# 1-Schematic_EMWAVER_ONE.net
KiCad netlist of a schematic drawn in EasyEDA
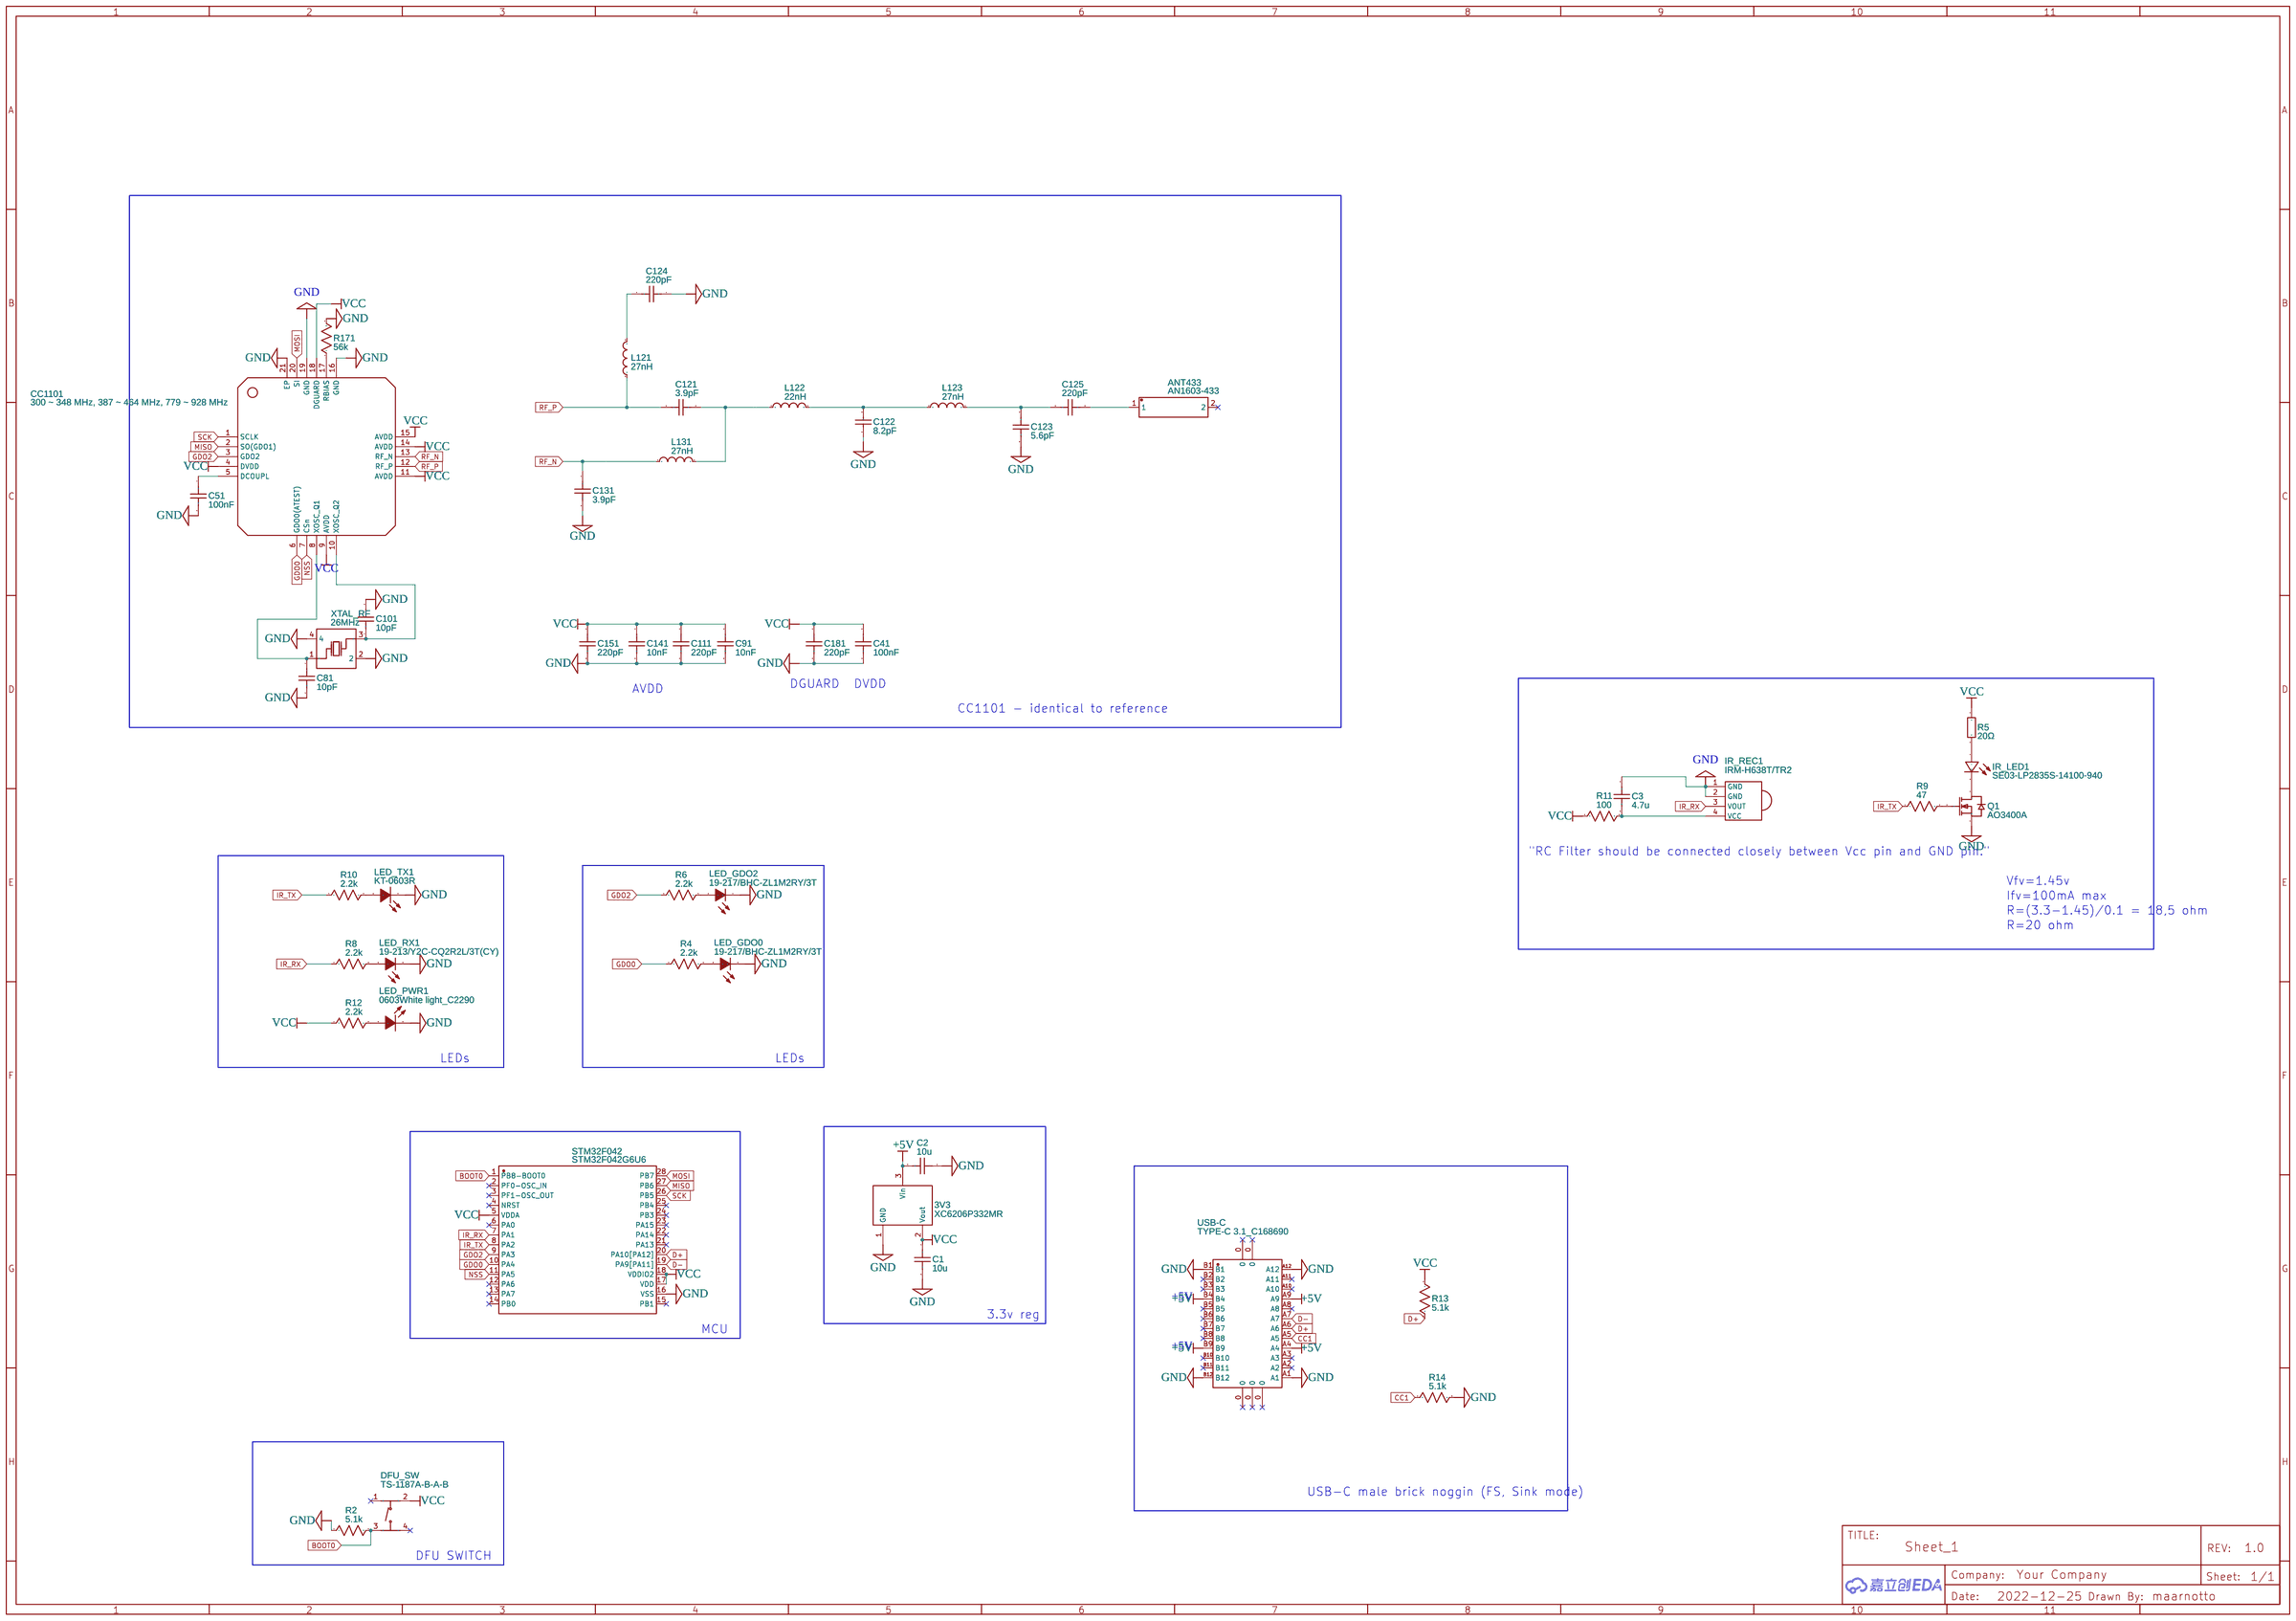
[diagram p0: schematic sheet]

(export (version "E")
  (design (tool "Eeschema 10.0.6"))
  (components
    (comp (ref "3V3")
      (value "XC6206P332MR")
      (fields (field (name "Manufacturer") "TOREX(特瑞仕)"))
      (libsource (lib "") (part "XC6206P332MR"))
    )
    (comp (ref "ANT433")
      (value "AN1603-433")
      (fields (field (name "Manufacturer") "rainsun(霖昱微)"))
      (libsource (lib "") (part "AN1603-433"))
    )
    (comp (ref "C1") (value "10u") (libsource (lib "") (part "C_0603_US")))
    (comp (ref "C2") (value "10u") (libsource (lib "") (part "C_0603_US_1")))
    (comp (ref "C3") (value "4.7u") (libsource (lib "") (part "C_0603_US")))
    (comp (ref "C41") (value "100nF") (libsource (lib "") (part "C_0402_US")))
    (comp (ref "C51") (value "100nF") (libsource (lib "") (part "C_0402_US")))
    (comp (ref "C81") (value "10pF") (libsource (lib "") (part "C_0402_US")))
    (comp (ref "C91") (value "10nF") (libsource (lib "") (part "C_0402_US")))
    (comp (ref "C101") (value "10pF") (libsource (lib "") (part "C_0402_US_2")))
    (comp (ref "C111") (value "220pF") (libsource (lib "") (part "C_0402_US")))
    (comp (ref "C121") (value "3.9pF") (libsource (lib "") (part "C_0402_US_1")))
    (comp (ref "C122")
      (value "8.2pF")
      (fields (field (name "Manufacturer Part") "0402CG8R2C500NT") (field (name "Manufacturer") "FH(风华)"))
      (libsource (lib "") (part "0402CG8R2C500NT"))
    )
    (comp (ref "C123") (value "5.6pF") (libsource (lib "") (part "C_0402_US")))
    (comp (ref "C124") (value "220pF") (libsource (lib "") (part "C_0402_US_1")))
    (comp (ref "C125") (value "220pF") (libsource (lib "") (part "C_0402_US_1")))
    (comp (ref "C131") (value "3.9pF") (libsource (lib "") (part "C_0402_US")))
    (comp (ref "C141") (value "10nF") (libsource (lib "") (part "C_0402_US")))
    (comp (ref "C151") (value "220pF") (libsource (lib "") (part "C_0402_US")))
    (comp (ref "C181") (value "220pF") (libsource (lib "") (part "C_0402_US")))
    (comp (ref "CC1101")
      (value "300 ~ 348 MHz, 387 ~ 464 MHz, 779 ~ 928 MHz")
      (fields (field (name "Manufacturer Part") "CC1101RGPR") (field (name "Manufacturer") "TI(德州仪器)"))
      (libsource (lib "") (part "CC1101RGPR"))
    )
    (comp (ref "DFU_SW")
      (value "TS-1187A-B-A-B")
      (fields (field (name "Manufacturer") "XKB Connectivity(中国星坤)"))
      (libsource (lib "") (part "TS-1187A-B-A-B"))
    )
    (comp (ref "IR_LED1")
      (value "SE03-LP2835S-14100-940")
      (fields (field (name "Manufacturer") "XSSY(旭晟)"))
      (libsource (lib "") (part "SE03-LP2835S-14100-940"))
    )
    (comp (ref "IR_REC1")
      (value "IRM-H638T/TR2")
      (fields (field (name "Manufacturer") "EVERLIGHT(亿光)"))
      (libsource (lib "") (part "IRM-H638T/TR2"))
    )
    (comp (ref "L121") (value "27nH") (libsource (lib "") (part "L0402_US_1")))
    (comp (ref "L122") (value "22nH") (libsource (lib "") (part "L0402_US")))
    (comp (ref "L123") (value "27nH") (libsource (lib "") (part "L0402_US")))
    (comp (ref "L131") (value "27nH") (libsource (lib "") (part "L0402_US")))
    (comp (ref "LED_GDO0")
      (value "19-217/BHC-ZL1M2RY/3T")
      (fields (field (name "Manufacturer") "EVERLIGHT(亿光)"))
      (libsource (lib "") (part "19-217/BHC-ZL1M2RY/3T"))
    )
    (comp (ref "LED_GDO2")
      (value "19-217/BHC-ZL1M2RY/3T")
      (fields (field (name "Manufacturer") "EVERLIGHT(亿光)"))
      (libsource (lib "") (part "19-217/BHC-ZL1M2RY/3T"))
    )
    (comp (ref "LED_PWR1")
      (value "0603White light_C2290")
      (fields (field (name "Manufacturer Part") "KT-0603白灯"))
      (libsource (lib "") (part "0603White light_C2290"))
    )
    (comp (ref "LED_RX1")
      (value "19-213/Y2C-CQ2R2L/3T(CY)")
      (fields (field (name "Manufacturer") "EVERLIGHT(亿光)"))
      (libsource (lib "") (part "19-213/Y2C-CQ2R2L/3T(CY)"))
    )
    (comp (ref "LED_TX1")
      (value "KT-0603R")
      (fields (field (name "Manufacturer") "KENTO"))
      (libsource (lib "") (part "KT-0603R"))
    )
    (comp (ref "Q1")
      (value "AO3400A")
      (fields (field (name "Manufacturer") "AOS"))
      (libsource (lib "") (part "AO3400A"))
    )
    (comp (ref "R2") (value "5.1k") (libsource (lib "") (part "R_0603_US")))
    (comp (ref "R4") (value "2.2k") (libsource (lib "") (part "R_0603_US")))
    (comp (ref "R5")
      (value "20Ω")
      (fields
        (field (name "Manufacturer Part") "1206W4F200JT5E")
        (field (name "Manufacturer") "UNI-ROYAL(厚声)")
      )
      (libsource (lib "") (part "1206W4F200JT5E"))
    )
    (comp (ref "R6") (value "2.2k") (libsource (lib "") (part "R_0603_US")))
    (comp (ref "R8") (value "2.2k") (libsource (lib "") (part "R_0603_US")))
    (comp (ref "R9") (value "47") (libsource (lib "") (part "R_0603_US")))
    (comp (ref "R10") (value "2.2k") (libsource (lib "") (part "R_0603_US")))
    (comp (ref "R11") (value "100") (libsource (lib "") (part "R_0603_US")))
    (comp (ref "R12") (value "2.2k") (libsource (lib "") (part "R_0603_US")))
    (comp (ref "R13") (value "5.1k") (libsource (lib "") (part "R_0603_US_1")))
    (comp (ref "R14") (value "5.1k") (libsource (lib "") (part "R_0603_US")))
    (comp (ref "R171") (value "56k") (libsource (lib "") (part "R_0402_US")))
    (comp (ref "STM32F042")
      (value "STM32F042G6U6")
      (fields (field (name "Manufacturer") "ST(意法半导体)"))
      (libsource (lib "") (part "STM32F042G6U6"))
    )
    (comp (ref "USB-C")
      (value "TYPE-C 3.1_C168690")
      (fields (field (name "Manufacturer Part") "918-118A2021Y40000") (field (name "Manufacturer") "精拓金"))
      (libsource (lib "") (part "TYPE-C 3.1_C168690"))
    )
    (comp (ref "XTAL_RF")
      (value "26MHz")
      (fields (field (name "Manufacturer Part") "3S26000333") (field (name "Manufacturer") "YL(惠伦晶体)"))
      (libsource (lib "") (part "3S26000333"))
    )
  )
  (nets
    (net (code "1") (name "+5V") (class "Default")
      (node (ref "3V3") (pin "3") (pinfunction "Vin_3") (pintype "unspecified"))
      (node (ref "C2") (pin "2") (pinfunction "2_2") (pintype "unspecified"))
      (node (ref "USB-C") (pin "A4") (pinfunction "A4_A4") (pintype "unspecified"))
      (node (ref "USB-C") (pin "A9") (pinfunction "A9_A9") (pintype "unspecified"))
      (node (ref "USB-C") (pin "B4") (pinfunction "B4_B4") (pintype "unspecified"))
      (node (ref "USB-C") (pin "B9") (pinfunction "B9_B9") (pintype "unspecified"))
    )
    (net (code "2") (name "BOOT0") (class "Default")
      (node (ref "DFU_SW") (pin "3") (pinfunction "C_3") (pintype "unspecified"))
      (node (ref "R2") (pin "2") (pinfunction "2_2") (pintype "unspecified"))
      (node (ref "STM32F042") (pin "1") (pinfunction "PB8-BOOT0_1") (pintype "unspecified"))
    )
    (net (code "3") (name "CC1") (class "Default")
      (node (ref "R14") (pin "1") (pinfunction "1_1") (pintype "unspecified"))
      (node (ref "USB-C") (pin "A5") (pinfunction "A5_A5") (pintype "unspecified"))
    )
    (net (code "4") (name "D+") (class "Default")
      (node (ref "R13") (pin "2") (pinfunction "2_2") (pintype "unspecified"))
      (node (ref "STM32F042") (pin "20") (pinfunction "PA10[PA12]_20") (pintype "unspecified"))
      (node (ref "USB-C") (pin "A6") (pinfunction "A6_A6") (pintype "unspecified"))
    )
    (net (code "5") (name "D-") (class "Default")
      (node (ref "STM32F042") (pin "19") (pinfunction "PA9[PA11]_19") (pintype "unspecified"))
      (node (ref "USB-C") (pin "A7") (pinfunction "A7_A7") (pintype "unspecified"))
    )
    (net (code "6") (name "GDO0") (class "Default")
      (node (ref "CC1101") (pin "6") (pinfunction "GDO0(ATEST)_6") (pintype "unspecified"))
      (node (ref "R4") (pin "1") (pinfunction "1_1") (pintype "unspecified"))
      (node (ref "STM32F042") (pin "10") (pinfunction "PA4_10") (pintype "unspecified"))
    )
    (net (code "7") (name "GDO2") (class "Default")
      (node (ref "CC1101") (pin "3") (pinfunction "GDO2_3") (pintype "unspecified"))
      (node (ref "R6") (pin "1") (pinfunction "1_1") (pintype "unspecified"))
      (node (ref "STM32F042") (pin "9") (pinfunction "PA3_9") (pintype "unspecified"))
    )
    (net (code "8") (name "GND") (class "Default")
      (node (ref "3V3") (pin "1") (pinfunction "GND_1") (pintype "unspecified"))
      (node (ref "C1") (pin "2") (pinfunction "2_2") (pintype "unspecified"))
      (node (ref "C101") (pin "2") (pinfunction "2_2") (pintype "unspecified"))
      (node (ref "C111") (pin "2") (pinfunction "2_2") (pintype "unspecified"))
      (node (ref "C122") (pin "1") (pinfunction "1_1") (pintype "input"))
      (node (ref "C123") (pin "2") (pinfunction "2_2") (pintype "unspecified"))
      (node (ref "C124") (pin "1") (pinfunction "1_1") (pintype "unspecified"))
      (node (ref "C131") (pin "2") (pinfunction "2_2") (pintype "unspecified"))
      (node (ref "C141") (pin "2") (pinfunction "2_2") (pintype "unspecified"))
      (node (ref "C151") (pin "2") (pinfunction "2_2") (pintype "unspecified"))
      (node (ref "C181") (pin "2") (pinfunction "2_2") (pintype "unspecified"))
      (node (ref "C2") (pin "1") (pinfunction "1_1") (pintype "unspecified"))
      (node (ref "C3") (pin "1") (pinfunction "1_1") (pintype "unspecified"))
      (node (ref "C41") (pin "2") (pinfunction "2_2") (pintype "unspecified"))
      (node (ref "C51") (pin "2") (pinfunction "2_2") (pintype "unspecified"))
      (node (ref "C81") (pin "2") (pinfunction "2_2") (pintype "unspecified"))
      (node (ref "C91") (pin "2") (pinfunction "2_2") (pintype "unspecified"))
      (node (ref "CC1101") (pin "16") (pinfunction "GND_16") (pintype "unspecified"))
      (node (ref "CC1101") (pin "19") (pinfunction "GND_19") (pintype "unspecified"))
      (node (ref "CC1101") (pin "21") (pinfunction "EP_21") (pintype "unspecified"))
      (node (ref "IR_REC1") (pin "1") (pinfunction "GND_1") (pintype "input"))
      (node (ref "IR_REC1") (pin "2") (pinfunction "GND_2") (pintype "input"))
      (node (ref "LED_GDO0") (pin "1") (pinfunction "C_1") (pintype "input"))
      (node (ref "LED_GDO2") (pin "1") (pinfunction "C_1") (pintype "input"))
      (node (ref "LED_PWR1") (pin "2") (pinfunction "K_2") (pintype "unspecified"))
      (node (ref "LED_RX1") (pin "1") (pinfunction "C_1") (pintype "input"))
      (node (ref "LED_TX1") (pin "1") (pinfunction "K_1") (pintype "unspecified"))
      (node (ref "Q1") (pin "2") (pinfunction "S_2") (pintype "unspecified"))
      (node (ref "R14") (pin "2") (pinfunction "2_2") (pintype "unspecified"))
      (node (ref "R171") (pin "2") (pinfunction "2_2") (pintype "unspecified"))
      (node (ref "R2") (pin "1") (pinfunction "1_1") (pintype "unspecified"))
      (node (ref "STM32F042") (pin "16") (pinfunction "VSS_16") (pintype "unspecified"))
      (node (ref "USB-C") (pin "A1") (pinfunction "A1_A1") (pintype "unspecified"))
      (node (ref "USB-C") (pin "A12") (pinfunction "A12_A12") (pintype "unspecified"))
      (node (ref "USB-C") (pin "B1") (pinfunction "B1_B1") (pintype "unspecified"))
      (node (ref "USB-C") (pin "B12") (pinfunction "B12_B12") (pintype "unspecified"))
      (node (ref "XTAL_RF") (pin "2") (pinfunction "2_2") (pintype "unspecified"))
      (node (ref "XTAL_RF") (pin "4") (pinfunction "4_4") (pintype "unspecified"))
    )
    (net (code "9") (name "IR_RX") (class "Default")
      (node (ref "IR_REC1") (pin "3") (pinfunction "VOUT_3") (pintype "input"))
      (node (ref "R8") (pin "1") (pinfunction "1_1") (pintype "unspecified"))
      (node (ref "STM32F042") (pin "7") (pinfunction "PA1_7") (pintype "unspecified"))
    )
    (net (code "10") (name "IR_TX") (class "Default")
      (node (ref "R10") (pin "1") (pinfunction "1_1") (pintype "unspecified"))
      (node (ref "R9") (pin "1") (pinfunction "1_1") (pintype "unspecified"))
      (node (ref "STM32F042") (pin "8") (pinfunction "PA2_8") (pintype "unspecified"))
    )
    (net (code "11") (name "MISO") (class "Default")
      (node (ref "CC1101") (pin "2") (pinfunction "SO(GDO1)_2") (pintype "unspecified"))
      (node (ref "STM32F042") (pin "27") (pinfunction "PB6_27") (pintype "unspecified"))
    )
    (net (code "12") (name "MOSI") (class "Default")
      (node (ref "CC1101") (pin "20") (pinfunction "SI_20") (pintype "unspecified"))
      (node (ref "STM32F042") (pin "28") (pinfunction "PB7_28") (pintype "unspecified"))
    )
    (net (code "13") (name "NSS") (class "Default")
      (node (ref "CC1101") (pin "7") (pinfunction "CSn_7") (pintype "unspecified"))
      (node (ref "STM32F042") (pin "11") (pinfunction "PA5_11") (pintype "unspecified"))
    )
    (net (code "14") (name "Net-(ANT433-Pad1)") (class "Default")
      (node (ref "ANT433") (pin "1") (pinfunction "1_1") (pintype "unspecified"))
      (node (ref "C125") (pin "1") (pinfunction "1_1") (pintype "unspecified"))
    )
    (net (code "15") (name "Net-(C121-Pad1)") (class "Default")
      (node (ref "C121") (pin "1") (pinfunction "1_1") (pintype "unspecified"))
      (node (ref "L122") (pin "1") (pinfunction "1_1") (pintype "unspecified"))
      (node (ref "L131") (pin "2") (pinfunction "2_2") (pintype "unspecified"))
    )
    (net (code "16") (name "Net-(C122-Pad2)") (class "Default")
      (node (ref "C122") (pin "2") (pinfunction "2_2") (pintype "input"))
      (node (ref "L122") (pin "2") (pinfunction "2_2") (pintype "unspecified"))
      (node (ref "L123") (pin "1") (pinfunction "1_1") (pintype "unspecified"))
    )
    (net (code "17") (name "Net-(C123-Pad1)") (class "Default")
      (node (ref "C123") (pin "1") (pinfunction "1_1") (pintype "unspecified"))
      (node (ref "C125") (pin "2") (pinfunction "2_2") (pintype "unspecified"))
      (node (ref "L123") (pin "2") (pinfunction "2_2") (pintype "unspecified"))
    )
    (net (code "18") (name "Net-(C124-Pad2)") (class "Default")
      (node (ref "C124") (pin "2") (pinfunction "2_2") (pintype "unspecified"))
      (node (ref "L121") (pin "2") (pinfunction "2_2") (pintype "unspecified"))
    )
    (net (code "19") (name "Net-(CC1101-DCOUPL)") (class "Default")
      (node (ref "C51") (pin "1") (pinfunction "1_1") (pintype "unspecified"))
      (node (ref "CC1101") (pin "5") (pinfunction "DCOUPL_5") (pintype "unspecified"))
    )
    (net (code "20") (name "Net-(CC1101-RBIAS)") (class "Default")
      (node (ref "CC1101") (pin "17") (pinfunction "RBIAS_17") (pintype "unspecified"))
      (node (ref "R171") (pin "1") (pinfunction "1_1") (pintype "unspecified"))
    )
    (net (code "21") (name "Net-(CC1101-XOSC_Q1)") (class "Default")
      (node (ref "C81") (pin "1") (pinfunction "1_1") (pintype "unspecified"))
      (node (ref "CC1101") (pin "8") (pinfunction "XOSC_Q1_8") (pintype "unspecified"))
      (node (ref "XTAL_RF") (pin "1") (pinfunction "OSC1_1") (pintype "unspecified"))
    )
    (net (code "22") (name "Net-(CC1101-XOSC_Q2)") (class "Default")
      (node (ref "C101") (pin "1") (pinfunction "1_1") (pintype "unspecified"))
      (node (ref "CC1101") (pin "10") (pinfunction "XOSC_Q2_10") (pintype "unspecified"))
      (node (ref "XTAL_RF") (pin "3") (pinfunction "OSC2_3") (pintype "unspecified"))
    )
    (net (code "23") (name "Net-(IR_LED1-A)") (class "Default")
      (node (ref "IR_LED1") (pin "1") (pinfunction "A_1") (pintype "unspecified"))
      (node (ref "R5") (pin "2") (pinfunction "2_2") (pintype "input"))
    )
    (net (code "24") (name "Net-(IR_LED1-C)") (class "Default")
      (node (ref "IR_LED1") (pin "2") (pinfunction "C_2") (pintype "unspecified"))
      (node (ref "Q1") (pin "3") (pinfunction "D_3") (pintype "unspecified"))
    )
    (net (code "25") (name "Net-(IR_REC1-VCC)") (class "Default")
      (node (ref "C3") (pin "2") (pinfunction "2_2") (pintype "unspecified"))
      (node (ref "IR_REC1") (pin "4") (pinfunction "VCC_4") (pintype "input"))
      (node (ref "R11") (pin "2") (pinfunction "2_2") (pintype "unspecified"))
    )
    (net (code "26") (name "Net-(LED_GDO0-A)") (class "Default")
      (node (ref "LED_GDO0") (pin "2") (pinfunction "A_2") (pintype "input"))
      (node (ref "R4") (pin "2") (pinfunction "2_2") (pintype "unspecified"))
    )
    (net (code "27") (name "Net-(LED_GDO2-A)") (class "Default")
      (node (ref "LED_GDO2") (pin "2") (pinfunction "A_2") (pintype "input"))
      (node (ref "R6") (pin "2") (pinfunction "2_2") (pintype "unspecified"))
    )
    (net (code "28") (name "Net-(LED_PWR1-A)") (class "Default")
      (node (ref "LED_PWR1") (pin "1") (pinfunction "A_1") (pintype "unspecified"))
      (node (ref "R12") (pin "2") (pinfunction "2_2") (pintype "unspecified"))
    )
    (net (code "29") (name "Net-(LED_RX1-A)") (class "Default")
      (node (ref "LED_RX1") (pin "2") (pinfunction "A_2") (pintype "input"))
      (node (ref "R8") (pin "2") (pinfunction "2_2") (pintype "unspecified"))
    )
    (net (code "30") (name "Net-(LED_TX1-A)") (class "Default")
      (node (ref "LED_TX1") (pin "2") (pinfunction "A_2") (pintype "unspecified"))
      (node (ref "R10") (pin "2") (pinfunction "2_2") (pintype "unspecified"))
    )
    (net (code "31") (name "Net-(Q1-G)") (class "Default")
      (node (ref "Q1") (pin "1") (pinfunction "G_1") (pintype "unspecified"))
      (node (ref "R9") (pin "2") (pinfunction "2_2") (pintype "unspecified"))
    )
    (net (code "32") (name "RF_N") (class "Default")
      (node (ref "C131") (pin "1") (pinfunction "1_1") (pintype "unspecified"))
      (node (ref "CC1101") (pin "13") (pinfunction "RF_N_13") (pintype "unspecified"))
      (node (ref "L131") (pin "1") (pinfunction "1_1") (pintype "unspecified"))
    )
    (net (code "33") (name "RF_P") (class "Default")
      (node (ref "C121") (pin "2") (pinfunction "2_2") (pintype "unspecified"))
      (node (ref "CC1101") (pin "12") (pinfunction "RF_P_12") (pintype "unspecified"))
      (node (ref "L121") (pin "1") (pinfunction "1_1") (pintype "unspecified"))
    )
    (net (code "34") (name "SCK") (class "Default")
      (node (ref "CC1101") (pin "1") (pinfunction "SCLK_1") (pintype "unspecified"))
      (node (ref "STM32F042") (pin "26") (pinfunction "PB5_26") (pintype "unspecified"))
    )
    (net (code "35") (name "VCC") (class "Default")
      (node (ref "3V3") (pin "2") (pinfunction "Vout_2") (pintype "unspecified"))
      (node (ref "C1") (pin "1") (pinfunction "1_1") (pintype "unspecified"))
      (node (ref "C111") (pin "1") (pinfunction "1_1") (pintype "unspecified"))
      (node (ref "C141") (pin "1") (pinfunction "1_1") (pintype "unspecified"))
      (node (ref "C151") (pin "1") (pinfunction "1_1") (pintype "unspecified"))
      (node (ref "C181") (pin "1") (pinfunction "1_1") (pintype "unspecified"))
      (node (ref "C41") (pin "1") (pinfunction "1_1") (pintype "unspecified"))
      (node (ref "C91") (pin "1") (pinfunction "1_1") (pintype "unspecified"))
      (node (ref "CC1101") (pin "11") (pinfunction "AVDD_11") (pintype "unspecified"))
      (node (ref "CC1101") (pin "14") (pinfunction "AVDD_14") (pintype "unspecified"))
      (node (ref "CC1101") (pin "15") (pinfunction "AVDD_15") (pintype "unspecified"))
      (node (ref "CC1101") (pin "18") (pinfunction "DGUARD_18") (pintype "unspecified"))
      (node (ref "CC1101") (pin "4") (pinfunction "DVDD_4") (pintype "unspecified"))
      (node (ref "CC1101") (pin "9") (pinfunction "AVDD_9") (pintype "unspecified"))
      (node (ref "DFU_SW") (pin "2") (pinfunction "B_2") (pintype "unspecified"))
      (node (ref "R11") (pin "1") (pinfunction "1_1") (pintype "unspecified"))
      (node (ref "R12") (pin "1") (pinfunction "1_1") (pintype "unspecified"))
      (node (ref "R13") (pin "1") (pinfunction "1_1") (pintype "unspecified"))
      (node (ref "R5") (pin "1") (pinfunction "1_1") (pintype "input"))
      (node (ref "STM32F042") (pin "17") (pinfunction "VDD_17") (pintype "unspecified"))
      (node (ref "STM32F042") (pin "18") (pinfunction "VDDIO2_18") (pintype "unspecified"))
      (node (ref "STM32F042") (pin "5") (pinfunction "VDDA_5") (pintype "unspecified"))
    )
    (net (code "36") (name "unconnected-(ANT433-Pad2)") (class "Default")
      (node (ref "ANT433") (pin "2") (pinfunction "2_2") (pintype "unspecified+no_connect"))
    )
    (net (code "37") (name "unconnected-(DFU_SW-A-Pad1)") (class "Default")
      (node (ref "DFU_SW") (pin "1") (pinfunction "A_1") (pintype "unspecified+no_connect"))
    )
    (net (code "38") (name "unconnected-(DFU_SW-D-Pad4)") (class "Default")
      (node (ref "DFU_SW") (pin "4") (pinfunction "D_4") (pintype "unspecified+no_connect"))
    )
    (net (code "39") (name "unconnected-(STM32F042-NRST-Pad4)") (class "Default")
      (node (ref "STM32F042") (pin "4") (pinfunction "NRST_4") (pintype "unspecified+no_connect"))
    )
    (net (code "40") (name "unconnected-(STM32F042-PA0-Pad6)") (class "Default")
      (node (ref "STM32F042") (pin "6") (pinfunction "PA0_6") (pintype "unspecified+no_connect"))
    )
    (net (code "41") (name "unconnected-(STM32F042-PA6-Pad12)") (class "Default")
      (node (ref "STM32F042") (pin "12") (pinfunction "PA6_12") (pintype "unspecified+no_connect"))
    )
    (net (code "42") (name "unconnected-(STM32F042-PA7-Pad13)") (class "Default")
      (node (ref "STM32F042") (pin "13") (pinfunction "PA7_13") (pintype "unspecified+no_connect"))
    )
    (net (code "43") (name "unconnected-(STM32F042-PA13-Pad21)") (class "Default")
      (node (ref "STM32F042") (pin "21") (pinfunction "PA13_21") (pintype "unspecified+no_connect"))
    )
    (net (code "44") (name "unconnected-(STM32F042-PA14-Pad22)") (class "Default")
      (node (ref "STM32F042") (pin "22") (pinfunction "PA14_22") (pintype "unspecified+no_connect"))
    )
    (net (code "45") (name "unconnected-(STM32F042-PA15-Pad23)") (class "Default")
      (node (ref "STM32F042") (pin "23") (pinfunction "PA15_23") (pintype "unspecified+no_connect"))
    )
    (net (code "46") (name "unconnected-(STM32F042-PB0-Pad14)") (class "Default")
      (node (ref "STM32F042") (pin "14") (pinfunction "PB0_14") (pintype "unspecified+no_connect"))
    )
    (net (code "47") (name "unconnected-(STM32F042-PB1-Pad15)") (class "Default")
      (node (ref "STM32F042") (pin "15") (pinfunction "PB1_15") (pintype "unspecified+no_connect"))
    )
    (net (code "48") (name "unconnected-(STM32F042-PB3-Pad24)") (class "Default")
      (node (ref "STM32F042") (pin "24") (pinfunction "PB3_24") (pintype "unspecified+no_connect"))
    )
    (net (code "49") (name "unconnected-(STM32F042-PB4-Pad25)") (class "Default")
      (node (ref "STM32F042") (pin "25") (pinfunction "PB4_25") (pintype "unspecified+no_connect"))
    )
    (net (code "50") (name "unconnected-(STM32F042-PF0-OSC_IN-Pad2)") (class "Default")
      (node (ref "STM32F042") (pin "2") (pinfunction "PF0-OSC_IN_2") (pintype "unspecified+no_connect"))
    )
    (net (code "51") (name "unconnected-(STM32F042-PF1-OSC_OUT-Pad3)") (class "Default")
      (node (ref "STM32F042") (pin "3") (pinfunction "PF1-OSC_OUT_3") (pintype "unspecified+no_connect"))
    )
    (net (code "52") (name "unconnected-(USB-C-Pad0)") (class "Default")
      (node (ref "USB-C") (pin "0") (pinfunction "0_0") (pintype "unspecified+no_connect"))
    )
    (net (code "53") (name "unconnected-(USB-C-Pad0)_1") (class "Default")
      (node (ref "USB-C") (pin "0") (pinfunction "0_0") (pintype "unspecified+no_connect"))
    )
    (net (code "54") (name "unconnected-(USB-C-Pad0)_2") (class "Default")
      (node (ref "USB-C") (pin "0") (pinfunction "0_0") (pintype "unspecified+no_connect"))
    )
    (net (code "55") (name "unconnected-(USB-C-Pad0)_3") (class "Default")
      (node (ref "USB-C") (pin "0") (pinfunction "0_0") (pintype "unspecified+no_connect"))
    )
    (net (code "56") (name "unconnected-(USB-C-Pad0)_4") (class "Default")
      (node (ref "USB-C") (pin "0") (pinfunction "0_0") (pintype "unspecified+no_connect"))
    )
    (net (code "57") (name "unconnected-(USB-C-PadA2)") (class "Default")
      (node (ref "USB-C") (pin "A2") (pinfunction "A2_A2") (pintype "unspecified+no_connect"))
    )
    (net (code "58") (name "unconnected-(USB-C-PadA3)") (class "Default")
      (node (ref "USB-C") (pin "A3") (pinfunction "A3_A3") (pintype "unspecified+no_connect"))
    )
    (net (code "59") (name "unconnected-(USB-C-PadA8)") (class "Default")
      (node (ref "USB-C") (pin "A8") (pinfunction "A8_A8") (pintype "unspecified+no_connect"))
    )
    (net (code "60") (name "unconnected-(USB-C-PadA10)") (class "Default")
      (node (ref "USB-C") (pin "A10") (pinfunction "A10_A10") (pintype "unspecified+no_connect"))
    )
    (net (code "61") (name "unconnected-(USB-C-PadA11)") (class "Default")
      (node (ref "USB-C") (pin "A11") (pinfunction "A11_A11") (pintype "unspecified+no_connect"))
    )
    (net (code "62") (name "unconnected-(USB-C-PadB2)") (class "Default")
      (node (ref "USB-C") (pin "B2") (pinfunction "B2_B2") (pintype "unspecified+no_connect"))
    )
    (net (code "63") (name "unconnected-(USB-C-PadB3)") (class "Default")
      (node (ref "USB-C") (pin "B3") (pinfunction "B3_B3") (pintype "unspecified+no_connect"))
    )
    (net (code "64") (name "unconnected-(USB-C-PadB5)") (class "Default")
      (node (ref "USB-C") (pin "B5") (pinfunction "B5_B5") (pintype "unspecified+no_connect"))
    )
    (net (code "65") (name "unconnected-(USB-C-PadB6)") (class "Default")
      (node (ref "USB-C") (pin "B6") (pinfunction "B6_B6") (pintype "unspecified+no_connect"))
    )
    (net (code "66") (name "unconnected-(USB-C-PadB7)") (class "Default")
      (node (ref "USB-C") (pin "B7") (pinfunction "B7_B7") (pintype "unspecified+no_connect"))
    )
    (net (code "67") (name "unconnected-(USB-C-PadB8)") (class "Default")
      (node (ref "USB-C") (pin "B8") (pinfunction "B8_B8") (pintype "unspecified+no_connect"))
    )
    (net (code "68") (name "unconnected-(USB-C-PadB10)") (class "Default")
      (node (ref "USB-C") (pin "B10") (pinfunction "B10_B10") (pintype "unspecified+no_connect"))
    )
    (net (code "69") (name "unconnected-(USB-C-PadB11)") (class "Default")
      (node (ref "USB-C") (pin "B11") (pinfunction "B11_B11") (pintype "unspecified+no_connect"))
    )
  )
)
